# MySXSenors.net
KiCad netlist of a schematic drawn in EAGLE
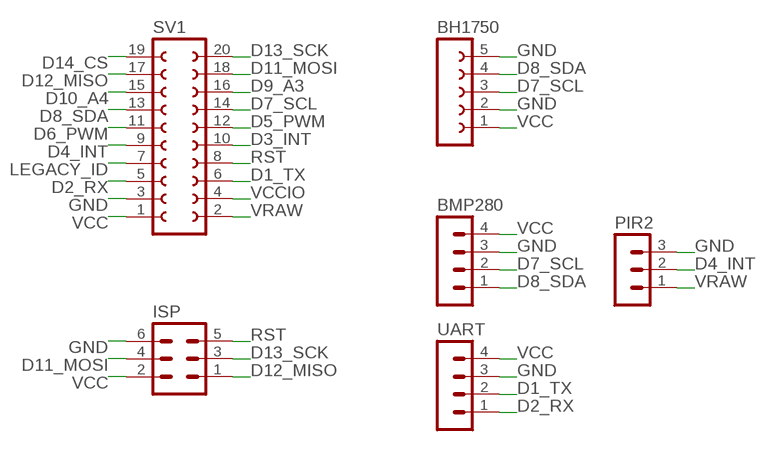
[diagram p0: schematic, sheet 1]

(export (version "E")
  (design (tool "Eeschema 10.0.6"))
  (components
    (comp (ref "BH1750")
      (value "FE05-1")
      (footprint "eagle-import:FE05-1")
      (libsource (lib "eagle-import") (part "FE05-1"))
    )
    (comp (ref "BMP280")
      (value "MA04-1")
      (footprint "eagle-import:MA04-1")
      (libsource (lib "eagle-import") (part "MA04-1"))
    )
    (comp (ref "ISP")
      (value "MA03-2")
      (footprint "eagle-import:MA03-2")
      (libsource (lib "eagle-import") (part "MA03-2"))
    )
    (comp (ref "PIR2")
      (value "MA03-1")
      (footprint "eagle-import:MA03-1")
      (libsource (lib "eagle-import") (part "MA03-1"))
    )
    (comp (ref "SV1")
      (value "FE10-2")
      (footprint "eagle-import:FE10-2")
      (libsource (lib "eagle-import") (part "FE10-2"))
    )
    (comp (ref "UART")
      (value "MA04-1")
      (footprint "eagle-import:MA04-1")
      (libsource (lib "eagle-import") (part "MA04-1"))
    )
  )
  (nets
    (net (code "1") (name "/D1_TX") (class "Default")
      (node (ref "SV1") (pin "6") (pinfunction "6_6") (pintype "passive"))
      (node (ref "UART") (pin "2") (pinfunction "2_2") (pintype "passive"))
    )
    (net (code "2") (name "/D2_RX") (class "Default")
      (node (ref "SV1") (pin "5") (pinfunction "5_5") (pintype "passive"))
      (node (ref "UART") (pin "1") (pinfunction "1_1") (pintype "passive"))
    )
    (net (code "3") (name "/D3_INT") (class "Default")
      (node (ref "SV1") (pin "10") (pinfunction "10_10") (pintype "passive"))
    )
    (net (code "4") (name "/D4_INT") (class "Default")
      (node (ref "PIR2") (pin "2") (pinfunction "2_2") (pintype "passive"))
      (node (ref "SV1") (pin "9") (pinfunction "9_9") (pintype "passive"))
    )
    (net (code "5") (name "/D5_PWM") (class "Default")
      (node (ref "SV1") (pin "12") (pinfunction "12_12") (pintype "passive"))
    )
    (net (code "6") (name "/D6_PWM") (class "Default")
      (node (ref "SV1") (pin "11") (pinfunction "11_11") (pintype "passive"))
    )
    (net (code "7") (name "/D7_SCL") (class "Default")
      (node (ref "BH1750") (pin "3") (pinfunction "3_3") (pintype "passive"))
      (node (ref "BMP280") (pin "2") (pinfunction "2_2") (pintype "passive"))
      (node (ref "SV1") (pin "14") (pinfunction "14_14") (pintype "passive"))
    )
    (net (code "8") (name "/D8_SDA") (class "Default")
      (node (ref "BH1750") (pin "4") (pinfunction "4_4") (pintype "passive"))
      (node (ref "BMP280") (pin "1") (pinfunction "1_1") (pintype "passive"))
      (node (ref "SV1") (pin "13") (pinfunction "13_13") (pintype "passive"))
    )
    (net (code "9") (name "/D9_A3") (class "Default")
      (node (ref "SV1") (pin "16") (pinfunction "16_16") (pintype "passive"))
    )
    (net (code "10") (name "/D10_A4") (class "Default")
      (node (ref "SV1") (pin "15") (pinfunction "15_15") (pintype "passive"))
    )
    (net (code "11") (name "/D11_MOSI") (class "Default")
      (node (ref "ISP") (pin "4") (pinfunction "4_4") (pintype "passive"))
      (node (ref "SV1") (pin "18") (pinfunction "18_18") (pintype "passive"))
    )
    (net (code "12") (name "/D12_MISO") (class "Default")
      (node (ref "ISP") (pin "1") (pinfunction "1_1") (pintype "passive"))
      (node (ref "SV1") (pin "17") (pinfunction "17_17") (pintype "passive"))
    )
    (net (code "13") (name "/D13_SCK") (class "Default")
      (node (ref "ISP") (pin "3") (pinfunction "3_3") (pintype "passive"))
      (node (ref "SV1") (pin "20") (pinfunction "20_20") (pintype "passive"))
    )
    (net (code "14") (name "/D14_CS") (class "Default")
      (node (ref "SV1") (pin "19") (pinfunction "19_19") (pintype "passive"))
    )
    (net (code "15") (name "/GND") (class "Default")
      (node (ref "BH1750") (pin "2") (pinfunction "2_2") (pintype "passive"))
      (node (ref "BH1750") (pin "5") (pinfunction "5_5") (pintype "passive"))
      (node (ref "BMP280") (pin "3") (pinfunction "3_3") (pintype "passive"))
      (node (ref "ISP") (pin "6") (pinfunction "6_6") (pintype "passive"))
      (node (ref "PIR2") (pin "3") (pinfunction "3_3") (pintype "passive"))
      (node (ref "SV1") (pin "3") (pinfunction "3_3") (pintype "passive"))
      (node (ref "UART") (pin "3") (pinfunction "3_3") (pintype "passive"))
    )
    (net (code "16") (name "/LEGACY_ID") (class "Default")
      (node (ref "SV1") (pin "7") (pinfunction "7_7") (pintype "passive"))
    )
    (net (code "17") (name "/RST") (class "Default")
      (node (ref "ISP") (pin "5") (pinfunction "5_5") (pintype "passive"))
      (node (ref "SV1") (pin "8") (pinfunction "8_8") (pintype "passive"))
    )
    (net (code "18") (name "/VCC") (class "Default")
      (node (ref "BH1750") (pin "1") (pinfunction "1_1") (pintype "passive"))
      (node (ref "BMP280") (pin "4") (pinfunction "4_4") (pintype "passive"))
      (node (ref "ISP") (pin "2") (pinfunction "2_2") (pintype "passive"))
      (node (ref "SV1") (pin "1") (pinfunction "1_1") (pintype "passive"))
      (node (ref "UART") (pin "4") (pinfunction "4_4") (pintype "passive"))
    )
    (net (code "19") (name "/VCCIO") (class "Default")
      (node (ref "SV1") (pin "4") (pinfunction "4_4") (pintype "passive"))
    )
    (net (code "20") (name "/VRAW") (class "Default")
      (node (ref "PIR2") (pin "1") (pinfunction "1_1") (pintype "passive"))
      (node (ref "SV1") (pin "2") (pinfunction "2_2") (pintype "passive"))
    )
  )
)
